# CCR2.net
KiCad netlist of a schematic drawn in EAGLE
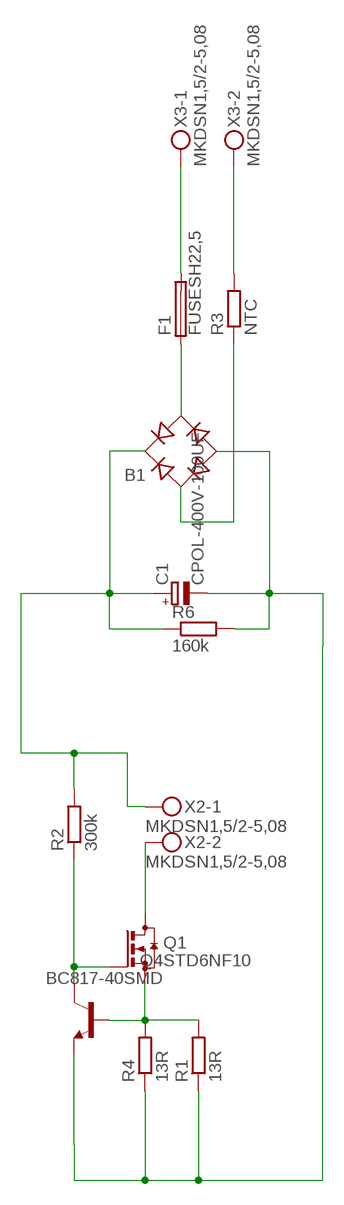
[diagram p0: schematic, sheet 1]

(export (version "E")
  (design (tool "Eeschema 10.0.6"))
  (components
    (comp (ref "B1")
      (value "RB1A")
      (footprint "eagle-import:RB1A")
      (libsource (lib "eagle-import") (part "RB1A"))
    )
    (comp (ref "C1")
      (value "CPOL-400V-100UF")
      (footprint "eagle-import:18_36.5_7.62")
      (libsource (lib "eagle-import") (part "CPOL-400V-100UF"))
    )
    (comp (ref "F1")
      (value "FUSESH22,5")
      (footprint "eagle-import:SH22,5")
      (libsource (lib "eagle-import") (part "FUSESH22,5"))
    )
    (comp (ref "Q1")
      (value "STD6NF10")
      (footprint "eagle-import:DPAK")
      (libsource (lib "eagle-import") (part "STD6NF10"))
    )
    (comp (ref "Q4")
      (value "BC817-40SMD")
      (footprint "eagle-import:SOT23-BEC")
      (libsource (lib "eagle-import") (part "BC817SMD-40"))
    )
    (comp (ref "R1")
      (value "13R")
      (footprint "eagle-import:0411_12")
      (libsource (lib "eagle-import") (part "R-EU_0411/12"))
    )
    (comp (ref "R2")
      (value "300k")
      (footprint "eagle-import:0411_12")
      (libsource (lib "eagle-import") (part "R-EU_0411/12"))
    )
    (comp (ref "R3")
      (value "NTC")
      (footprint "eagle-import:0309_10")
      (libsource (lib "eagle-import") (part "R-EU_0309/10"))
    )
    (comp (ref "R4")
      (value "13R")
      (footprint "eagle-import:0411_12")
      (libsource (lib "eagle-import") (part "R-EU_0411/12"))
    )
    (comp (ref "R6")
      (value "160k")
      (footprint "eagle-import:0204_7")
      (libsource (lib "eagle-import") (part "R-EU_0204/7"))
    )
    (comp (ref "X2")
      (value "MKDSN1,5/2-5,08")
      (footprint "eagle-import:MKDSN1,5_2-5,08")
      (libsource (lib "eagle-import") (part "MKDSN1,5/2-5,08"))
    )
    (comp (ref "X3")
      (value "MKDSN1,5/2-5,08")
      (footprint "eagle-import:MKDSN1,5_2-5,08")
      (libsource (lib "eagle-import") (part "MKDSN1,5/2-5,08"))
    )
  )
  (nets
    (net (code "1") (name "Net-(B1-PadAC1)") (class "Default")
      (node (ref "B1") (pin "AC1") (pinfunction "AC1_AC1") (pintype "passive"))
      (node (ref "R3") (pin "1") (pinfunction "1_1") (pintype "passive"))
    )
    (net (code "2") (name "Net-(B1-PadAC2)") (class "Default")
      (node (ref "B1") (pin "AC2") (pinfunction "AC2_AC2") (pintype "passive"))
      (node (ref "F1") (pin "1") (pinfunction "1_1") (pintype "passive"))
    )
    (net (code "3") (name "Net-(C1-+)") (class "Default")
      (node (ref "B1") (pin "+") (pinfunction "+_+") (pintype "passive"))
      (node (ref "C1") (pin "P$2") (pinfunction "+_P$2") (pintype "passive"))
      (node (ref "R2") (pin "2") (pinfunction "2_2") (pintype "passive"))
      (node (ref "R6") (pin "1") (pinfunction "1_1") (pintype "passive"))
      (node (ref "X2") (pin "1") (pinfunction "KL_1") (pintype "passive"))
    )
    (net (code "4") (name "Net-(C1--)") (class "Default")
      (node (ref "B1") (pin "-") (pinfunction "-_-") (pintype "passive"))
      (node (ref "C1") (pin "P$1") (pinfunction "-_P$1") (pintype "passive"))
      (node (ref "Q4") (pin "E") (pinfunction "E_E") (pintype "passive"))
      (node (ref "R1") (pin "1") (pinfunction "1_1") (pintype "passive"))
      (node (ref "R4") (pin "1") (pinfunction "1_1") (pintype "passive"))
      (node (ref "R6") (pin "2") (pinfunction "2_2") (pintype "passive"))
    )
    (net (code "5") (name "Net-(Q1-PadG)") (class "Default")
      (node (ref "Q1") (pin "G") (pinfunction "G_G") (pintype "passive"))
      (node (ref "Q4") (pin "C") (pinfunction "C_C") (pintype "passive"))
      (node (ref "R2") (pin "1") (pinfunction "1_1") (pintype "passive"))
    )
    (net (code "6") (name "Net-(Q1-PadS)") (class "Default")
      (node (ref "Q1") (pin "S") (pinfunction "S_S") (pintype "passive"))
      (node (ref "Q4") (pin "B") (pinfunction "B_B") (pintype "passive"))
      (node (ref "R1") (pin "2") (pinfunction "2_2") (pintype "passive"))
      (node (ref "R4") (pin "2") (pinfunction "2_2") (pintype "passive"))
    )
    (net (code "7") (name "Net-(X2B-KL)") (class "Default")
      (node (ref "Q1") (pin "D") (pinfunction "D_D") (pintype "passive"))
      (node (ref "X2") (pin "2") (pinfunction "KL_2") (pintype "passive"))
    )
    (net (code "8") (name "Net-(X3A-KL)") (class "Default")
      (node (ref "F1") (pin "2") (pinfunction "2_2") (pintype "passive"))
      (node (ref "X3") (pin "1") (pinfunction "KL_1") (pintype "passive"))
    )
    (net (code "9") (name "Net-(X3B-KL)") (class "Default")
      (node (ref "R3") (pin "2") (pinfunction "2_2") (pintype "passive"))
      (node (ref "X3") (pin "2") (pinfunction "KL_2") (pintype "passive"))
    )
  )
)
